# 04_BOOT.net
KiCad netlist of a schematic drawn in Altium Designer
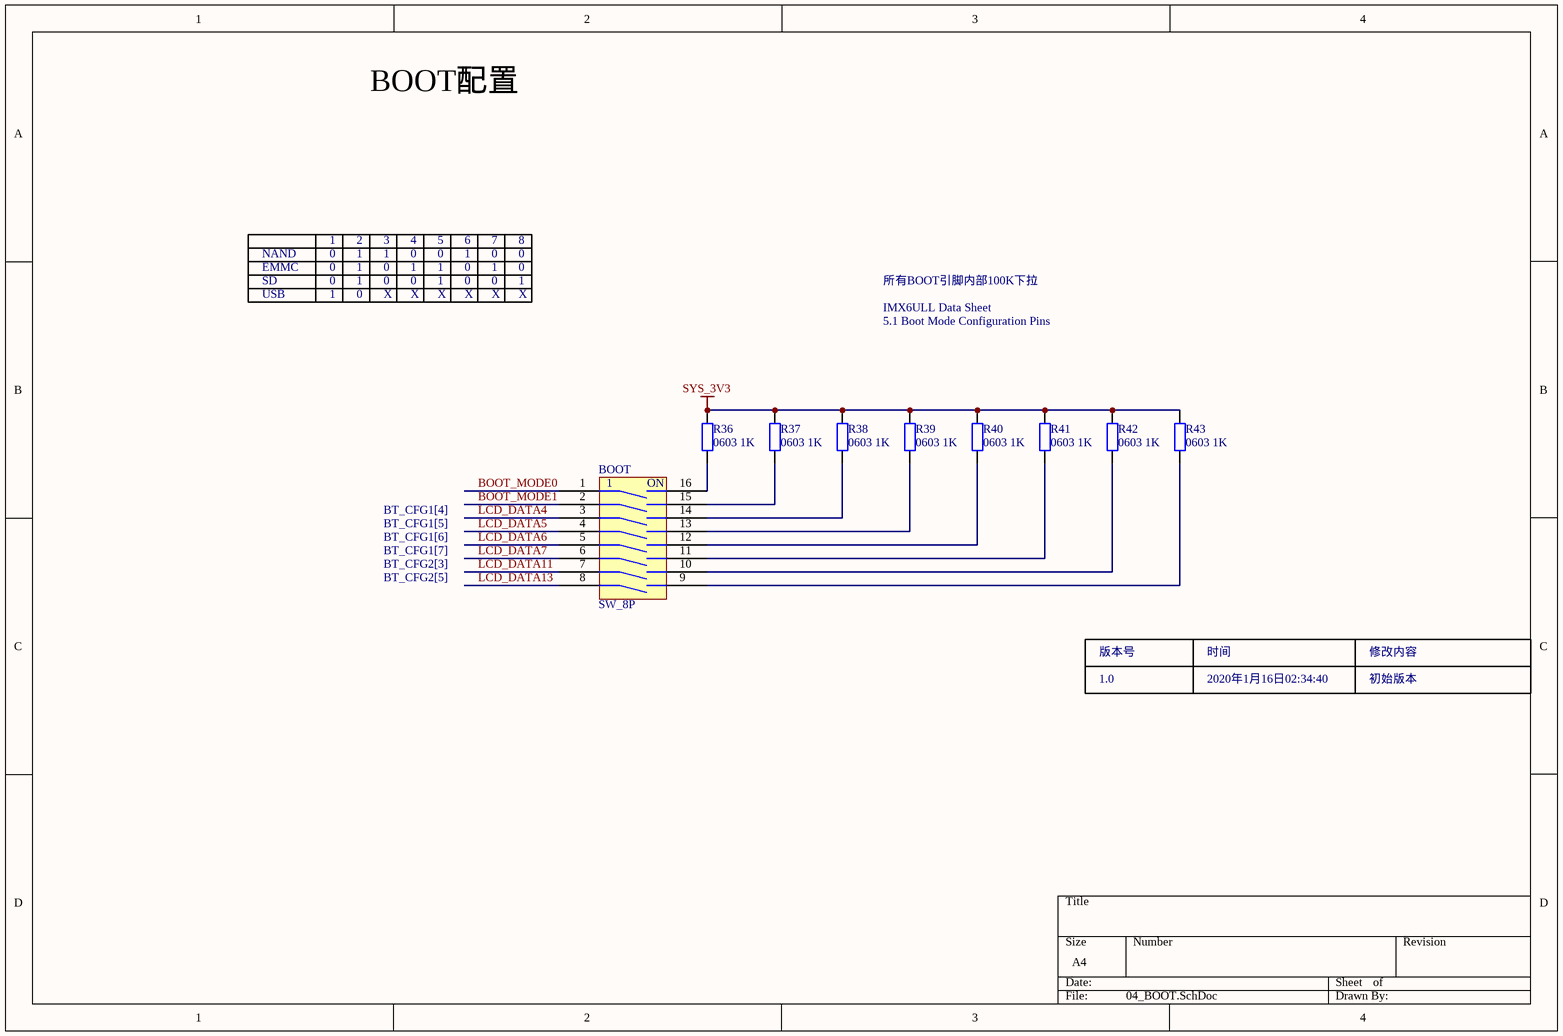
[diagram p0: 04_BOOT.SchDoc]

(export (version "E")
  (design (tool "Eeschema 10.0.6"))
  (components
    (comp (ref "BOOT")
      (value "SW_8P")
      (footprint "SW_8P_2.54")
      (libsource (lib "Integrated_Library2") (part "SW_8P"))
    )
    (comp (ref "R36")
      (value "0603 1K")
      (footprint "LC-0603_R")
      (description "贴片电阻")
      (libsource (lib "JLC") (part "0603 1.1KΩ (1101) 1%"))
    )
    (comp (ref "R37")
      (value "0603 1K")
      (footprint "LC-0603_R")
      (description "贴片电阻")
      (libsource (lib "JLC") (part "0603 1.1KΩ (1101) 1%"))
    )
    (comp (ref "R38")
      (value "0603 1K")
      (footprint "LC-0603_R")
      (description "贴片电阻")
      (libsource (lib "JLC") (part "0603 1.1KΩ (1101) 1%"))
    )
    (comp (ref "R39")
      (value "0603 1K")
      (footprint "LC-0603_R")
      (description "贴片电阻")
      (libsource (lib "JLC") (part "0603 1.1KΩ (1101) 1%"))
    )
    (comp (ref "R40")
      (value "0603 1K")
      (footprint "LC-0603_R")
      (description "贴片电阻")
      (libsource (lib "JLC") (part "0603 1.1KΩ (1101) 1%"))
    )
    (comp (ref "R41")
      (value "0603 1K")
      (footprint "LC-0603_R")
      (description "贴片电阻")
      (libsource (lib "JLC") (part "0603 1.1KΩ (1101) 1%"))
    )
    (comp (ref "R42")
      (value "0603 1K")
      (footprint "LC-0603_R")
      (description "贴片电阻")
      (libsource (lib "JLC") (part "0603 1.1KΩ (1101) 1%"))
    )
    (comp (ref "R43")
      (value "0603 1K")
      (footprint "LC-0603_R")
      (description "贴片电阻")
      (libsource (lib "JLC") (part "0603 1.1KΩ (1101) 1%"))
    )
  )
  (nets
    (net (code "1") (name "/BOOT_MODE0") (class "Default")
      (node (ref "BOOT") (pin "1") (pinfunction "1_1") (pintype "passive"))
    )
    (net (code "2") (name "/BOOT_MODE1") (class "Default")
      (node (ref "BOOT") (pin "2") (pinfunction "2_2") (pintype "passive"))
    )
    (net (code "3") (name "/LCD_DATA4") (class "Default")
      (node (ref "BOOT") (pin "3") (pinfunction "3_3") (pintype "passive"))
    )
    (net (code "4") (name "/LCD_DATA5") (class "Default")
      (node (ref "BOOT") (pin "4") (pinfunction "4_4") (pintype "passive"))
    )
    (net (code "5") (name "/LCD_DATA6") (class "Default")
      (node (ref "BOOT") (pin "5") (pinfunction "5_5") (pintype "passive"))
    )
    (net (code "6") (name "/LCD_DATA7") (class "Default")
      (node (ref "BOOT") (pin "6") (pinfunction "6_6") (pintype "passive"))
    )
    (net (code "7") (name "/LCD_DATA11") (class "Default")
      (node (ref "BOOT") (pin "7") (pinfunction "7_7") (pintype "passive"))
    )
    (net (code "8") (name "/LCD_DATA13") (class "Default")
      (node (ref "BOOT") (pin "8") (pinfunction "8_8") (pintype "passive"))
    )
    (net (code "9") (name "Net-(BOOT-Pad9)") (class "Default")
      (node (ref "BOOT") (pin "9") (pinfunction "9_9") (pintype "passive"))
      (node (ref "R43") (pin "1") (pinfunction "1_1") (pintype "passive"))
    )
    (net (code "10") (name "Net-(BOOT-Pad10)") (class "Default")
      (node (ref "BOOT") (pin "10") (pinfunction "10_10") (pintype "passive"))
      (node (ref "R42") (pin "1") (pinfunction "1_1") (pintype "passive"))
    )
    (net (code "11") (name "Net-(BOOT-Pad11)") (class "Default")
      (node (ref "BOOT") (pin "11") (pinfunction "11_11") (pintype "passive"))
      (node (ref "R41") (pin "1") (pinfunction "1_1") (pintype "passive"))
    )
    (net (code "12") (name "Net-(BOOT-Pad12)") (class "Default")
      (node (ref "BOOT") (pin "12") (pinfunction "12_12") (pintype "passive"))
      (node (ref "R40") (pin "1") (pinfunction "1_1") (pintype "passive"))
    )
    (net (code "13") (name "Net-(BOOT-Pad13)") (class "Default")
      (node (ref "BOOT") (pin "13") (pinfunction "13_13") (pintype "passive"))
      (node (ref "R39") (pin "1") (pinfunction "1_1") (pintype "passive"))
    )
    (net (code "14") (name "Net-(BOOT-Pad14)") (class "Default")
      (node (ref "BOOT") (pin "14") (pinfunction "14_14") (pintype "passive"))
      (node (ref "R38") (pin "1") (pinfunction "1_1") (pintype "passive"))
    )
    (net (code "15") (name "Net-(BOOT-Pad15)") (class "Default")
      (node (ref "BOOT") (pin "15") (pinfunction "15_15") (pintype "passive"))
      (node (ref "R37") (pin "1") (pinfunction "1_1") (pintype "passive"))
    )
    (net (code "16") (name "Net-(BOOT-Pad16)") (class "Default")
      (node (ref "BOOT") (pin "16") (pinfunction "16_16") (pintype "passive"))
      (node (ref "R36") (pin "1") (pinfunction "1_1") (pintype "passive"))
    )
    (net (code "17") (name "SYS_3V3") (class "Default")
      (node (ref "R36") (pin "2") (pinfunction "2_2") (pintype "passive"))
      (node (ref "R37") (pin "2") (pinfunction "2_2") (pintype "passive"))
      (node (ref "R38") (pin "2") (pinfunction "2_2") (pintype "passive"))
      (node (ref "R39") (pin "2") (pinfunction "2_2") (pintype "passive"))
      (node (ref "R40") (pin "2") (pinfunction "2_2") (pintype "passive"))
      (node (ref "R41") (pin "2") (pinfunction "2_2") (pintype "passive"))
      (node (ref "R42") (pin "2") (pinfunction "2_2") (pintype "passive"))
      (node (ref "R43") (pin "2") (pinfunction "2_2") (pintype "passive"))
    )
  )
)
